# Voltmetro_3Digit_HADDAOUI.net
KiCad netlist of a schematic drawn in EAGLE
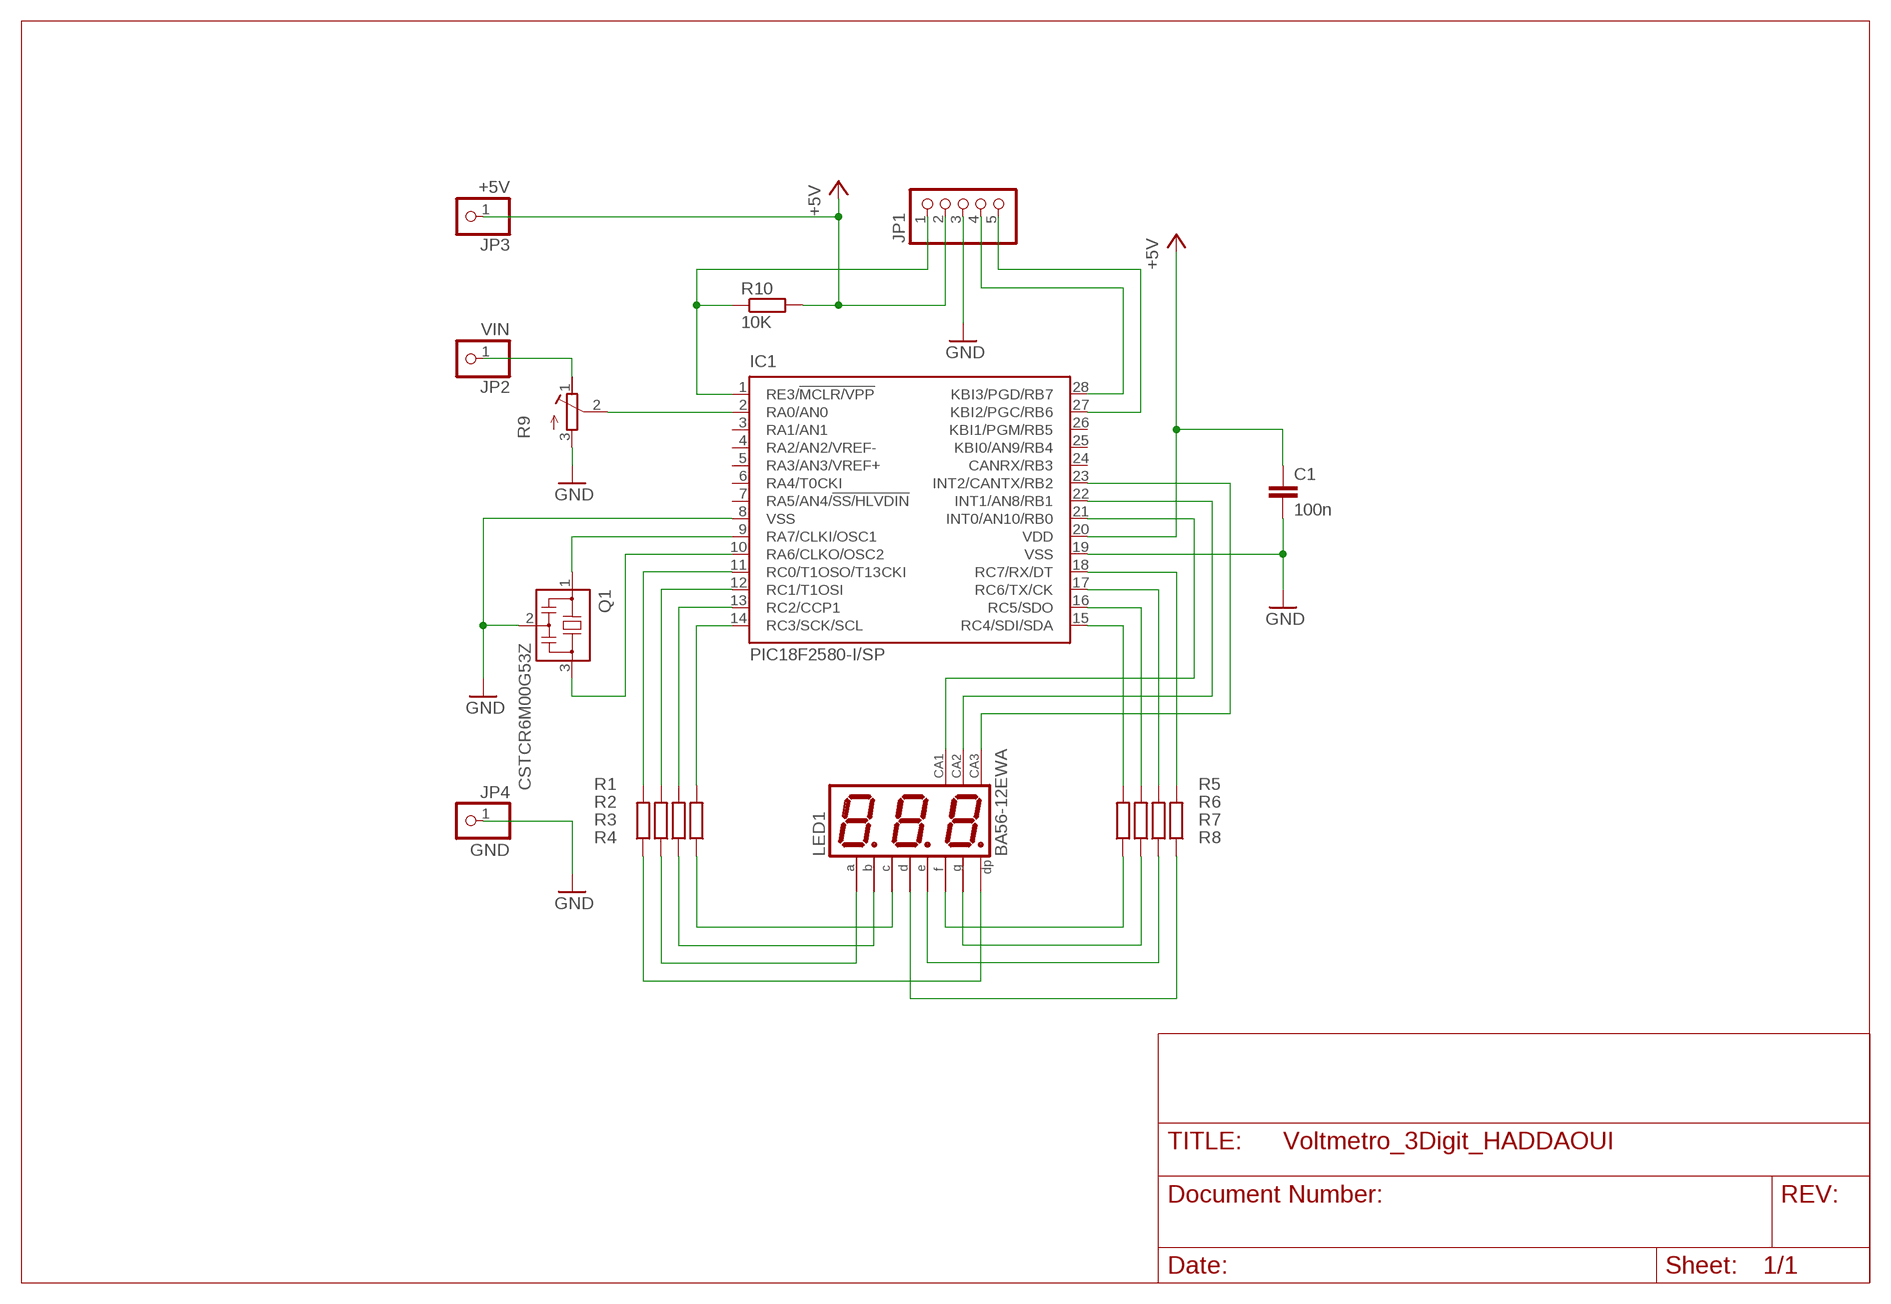
[diagram p0: schematic, sheet 1]

(export (version "E")
  (design (tool "Eeschema 10.0.6"))
  (components
    (comp (ref "C1")
      (value "100n")
      (footprint "eagle-import:C025-025X050")
      (libsource (lib "eagle-import") (part "C-EU025-025X050"))
    )
    (comp (ref "IC1")
      (value "PIC18F2580-I/SP")
      (footprint "eagle-import:DIL28-3")
      (fields (field (name "MF") "MICROCHIP"))
      (libsource (lib "eagle-import") (part "PIC18F280-I/SP5"))
    )
    (comp (ref "JP1")
      (value "PINHD-1X5")
      (footprint "eagle-import:1X05")
      (libsource (lib "eagle-import") (part "PINHD-1X5"))
    )
    (comp (ref "JP2")
      (value "VIN")
      (footprint "eagle-import:1X01")
      (libsource (lib "eagle-import") (part "PINHD-1X1"))
    )
    (comp (ref "JP3")
      (value "+5V")
      (footprint "eagle-import:1X01")
      (libsource (lib "eagle-import") (part "PINHD-1X1"))
    )
    (comp (ref "JP4")
      (value "GND")
      (footprint "eagle-import:1X01")
      (libsource (lib "eagle-import") (part "PINHD-1X1"))
    )
    (comp (ref "LED1")
      (value "BA56-12EWA")
      (footprint "eagle-import:BX56-12")
      (libsource (lib "eagle-import") (part "B?56-12WAAE"))
    )
    (comp (ref "Q1")
      (value "CSTCR6M00G53Z")
      (footprint "eagle-import:CSTCR6M")
      (fields (field (name "MPN") "CSTCR6M00G53-R0"))
      (libsource (lib "eagle-import") (part "CSTCR6M00G53Z"))
    )
    (comp (ref "R1")
      (value "R-EU_0204/7")
      (footprint "eagle-import:0204_7")
      (libsource (lib "eagle-import") (part "R-EU_0204/7"))
    )
    (comp (ref "R2")
      (value "R-EU_0204/7")
      (footprint "eagle-import:0204_7")
      (libsource (lib "eagle-import") (part "R-EU_0204/7"))
    )
    (comp (ref "R3")
      (value "R-EU_0204/7")
      (footprint "eagle-import:0204_7")
      (libsource (lib "eagle-import") (part "R-EU_0204/7"))
    )
    (comp (ref "R4")
      (value "R-EU_0204/7")
      (footprint "eagle-import:0204_7")
      (libsource (lib "eagle-import") (part "R-EU_0204/7"))
    )
    (comp (ref "R5")
      (value "R-EU_0204/7")
      (footprint "eagle-import:0204_7")
      (libsource (lib "eagle-import") (part "R-EU_0204/7"))
    )
    (comp (ref "R6")
      (value "R-EU_0204/7")
      (footprint "eagle-import:0204_7")
      (libsource (lib "eagle-import") (part "R-EU_0204/7"))
    )
    (comp (ref "R7")
      (value "R-EU_0204/7")
      (footprint "eagle-import:0204_7")
      (libsource (lib "eagle-import") (part "R-EU_0204/7"))
    )
    (comp (ref "R8")
      (value "R-EU_0204/7")
      (footprint "eagle-import:0204_7")
      (libsource (lib "eagle-import") (part "R-EU_0204/7"))
    )
    (comp (ref "R9")
      (value "R-TRIMM43P")
      (footprint "eagle-import:RTRIM43P")
      (libsource (lib "eagle-import") (part "R-TRIMM43P"))
    )
    (comp (ref "R10")
      (value "10K")
      (footprint "eagle-import:0204_7")
      (libsource (lib "eagle-import") (part "R-EU_0204/7"))
    )
  )
  (nets
    (net (code "1") (name "+5V") (class "Default")
      (node (ref "C1") (pin "1") (pinfunction "1_1") (pintype "passive"))
      (node (ref "IC1") (pin "20") (pinfunction "VDD_20") (pintype "power_in"))
      (node (ref "JP1") (pin "2") (pinfunction "2_2") (pintype "passive"))
      (node (ref "JP3") (pin "1") (pinfunction "1_1") (pintype "passive"))
      (node (ref "R10") (pin "2") (pinfunction "2_2") (pintype "passive"))
    )
    (net (code "2") (name "GND") (class "Default")
      (node (ref "C1") (pin "2") (pinfunction "2_2") (pintype "passive"))
      (node (ref "IC1") (pin "19") (pinfunction "VSS_19") (pintype "power_in"))
      (node (ref "IC1") (pin "8") (pinfunction "VSS_8") (pintype "power_in"))
      (node (ref "JP1") (pin "3") (pinfunction "3_3") (pintype "passive"))
      (node (ref "JP4") (pin "1") (pinfunction "1_1") (pintype "passive"))
      (node (ref "Q1") (pin "2") (pinfunction "2_2") (pintype "passive"))
      (node (ref "R9") (pin "3") (pinfunction "A_3") (pintype "passive"))
    )
    (net (code "3") (name "Net-(IC1-INT0{slash}AN10{slash}RB0)") (class "Default")
      (node (ref "IC1") (pin "21") (pinfunction "INT0/AN10/RB0_21") (pintype "bidirectional"))
      (node (ref "LED1") (pin "12") (pinfunction "CA_12") (pintype "passive"))
    )
    (net (code "4") (name "Net-(IC1-INT1{slash}AN8{slash}RB1)") (class "Default")
      (node (ref "IC1") (pin "22") (pinfunction "INT1/AN8/RB1_22") (pintype "bidirectional"))
      (node (ref "LED1") (pin "9") (pinfunction "CA_9") (pintype "passive"))
    )
    (net (code "5") (name "Net-(IC1-INT2{slash}CANTX{slash}RB2)") (class "Default")
      (node (ref "IC1") (pin "23") (pinfunction "INT2/CANTX/RB2_23") (pintype "bidirectional"))
      (node (ref "LED1") (pin "8") (pinfunction "CA_8") (pintype "passive"))
    )
    (net (code "6") (name "Net-(IC1-KBI2{slash}PGC{slash}RB6)") (class "Default")
      (node (ref "IC1") (pin "27") (pinfunction "KBI2/PGC/RB6_27") (pintype "bidirectional"))
      (node (ref "JP1") (pin "5") (pinfunction "5_5") (pintype "passive"))
    )
    (net (code "7") (name "Net-(IC1-KBI3{slash}PGD{slash}RB7)") (class "Default")
      (node (ref "IC1") (pin "28") (pinfunction "KBI3/PGD/RB7_28") (pintype "bidirectional"))
      (node (ref "JP1") (pin "4") (pinfunction "4_4") (pintype "passive"))
    )
    (net (code "8") (name "Net-(IC1-RA0{slash}AN0)") (class "Default")
      (node (ref "IC1") (pin "2") (pinfunction "RA0/AN0_2") (pintype "bidirectional"))
      (node (ref "R9") (pin "2") (pinfunction "S_2") (pintype "passive"))
    )
    (net (code "9") (name "Net-(IC1-RA6{slash}CLKO{slash}OSC2)") (class "Default")
      (node (ref "IC1") (pin "10") (pinfunction "RA6/CLKO/OSC2_10") (pintype "output"))
      (node (ref "Q1") (pin "3") (pinfunction "3_3") (pintype "passive"))
    )
    (net (code "10") (name "Net-(IC1-RA7{slash}CLKI{slash}OSC1)") (class "Default")
      (node (ref "IC1") (pin "9") (pinfunction "RA7/CLKI/OSC1_9") (pintype "input"))
      (node (ref "Q1") (pin "1") (pinfunction "1_1") (pintype "passive"))
    )
    (net (code "11") (name "Net-(IC1-RC0{slash}T1OSO{slash}T13CKI)") (class "Default")
      (node (ref "IC1") (pin "11") (pinfunction "RC0/T1OSO/T13CKI_11") (pintype "bidirectional"))
      (node (ref "R1") (pin "2") (pinfunction "2_2") (pintype "passive"))
    )
    (net (code "12") (name "Net-(IC1-RC1{slash}T1OSI)") (class "Default")
      (node (ref "IC1") (pin "12") (pinfunction "RC1/T1OSI_12") (pintype "bidirectional"))
      (node (ref "R2") (pin "2") (pinfunction "2_2") (pintype "passive"))
    )
    (net (code "13") (name "Net-(IC1-RC2{slash}CCP1)") (class "Default")
      (node (ref "IC1") (pin "13") (pinfunction "RC2/CCP1_13") (pintype "bidirectional"))
      (node (ref "R3") (pin "2") (pinfunction "2_2") (pintype "passive"))
    )
    (net (code "14") (name "Net-(IC1-RC3{slash}SCK{slash}SCL)") (class "Default")
      (node (ref "IC1") (pin "14") (pinfunction "RC3/SCK/SCL_14") (pintype "bidirectional"))
      (node (ref "R4") (pin "2") (pinfunction "2_2") (pintype "passive"))
    )
    (net (code "15") (name "Net-(IC1-RC4{slash}SDI{slash}SDA)") (class "Default")
      (node (ref "IC1") (pin "15") (pinfunction "RC4/SDI/SDA_15") (pintype "bidirectional"))
      (node (ref "R5") (pin "2") (pinfunction "2_2") (pintype "passive"))
    )
    (net (code "16") (name "Net-(IC1-RC5{slash}SDO)") (class "Default")
      (node (ref "IC1") (pin "16") (pinfunction "RC5/SDO_16") (pintype "bidirectional"))
      (node (ref "R6") (pin "2") (pinfunction "2_2") (pintype "passive"))
    )
    (net (code "17") (name "Net-(IC1-RC6{slash}TX{slash}CK)") (class "Default")
      (node (ref "IC1") (pin "17") (pinfunction "RC6/TX/CK_17") (pintype "bidirectional"))
      (node (ref "R7") (pin "2") (pinfunction "2_2") (pintype "passive"))
    )
    (net (code "18") (name "Net-(IC1-RC7{slash}RX{slash}DT)") (class "Default")
      (node (ref "IC1") (pin "18") (pinfunction "RC7/RX/DT_18") (pintype "bidirectional"))
      (node (ref "R8") (pin "2") (pinfunction "2_2") (pintype "passive"))
    )
    (net (code "19") (name "Net-(IC1-RE3{slash}~{MCLR{slash}VPP})") (class "Default")
      (node (ref "IC1") (pin "1") (pinfunction "RE3/~{MCLR/VPP}_1") (pintype "input"))
      (node (ref "JP1") (pin "1") (pinfunction "1_1") (pintype "passive"))
      (node (ref "R10") (pin "1") (pinfunction "1_1") (pintype "passive"))
    )
    (net (code "20") (name "Net-(LED1-A)") (class "Default")
      (node (ref "LED1") (pin "11") (pinfunction "A_11") (pintype "passive"))
      (node (ref "R2") (pin "1") (pinfunction "1_1") (pintype "passive"))
    )
    (net (code "21") (name "Net-(LED1-B)") (class "Default")
      (node (ref "LED1") (pin "7") (pinfunction "B_7") (pintype "passive"))
      (node (ref "R3") (pin "1") (pinfunction "1_1") (pintype "passive"))
    )
    (net (code "22") (name "Net-(LED1-C)") (class "Default")
      (node (ref "LED1") (pin "4") (pinfunction "C_4") (pintype "passive"))
      (node (ref "R4") (pin "1") (pinfunction "1_1") (pintype "passive"))
    )
    (net (code "23") (name "Net-(LED1-D)") (class "Default")
      (node (ref "LED1") (pin "2") (pinfunction "D_2") (pintype "passive"))
      (node (ref "R8") (pin "1") (pinfunction "1_1") (pintype "passive"))
    )
    (net (code "24") (name "Net-(LED1-DP)") (class "Default")
      (node (ref "LED1") (pin "3") (pinfunction "DP_3") (pintype "passive"))
      (node (ref "R1") (pin "1") (pinfunction "1_1") (pintype "passive"))
    )
    (net (code "25") (name "Net-(LED1-E)") (class "Default")
      (node (ref "LED1") (pin "1") (pinfunction "E_1") (pintype "passive"))
      (node (ref "R7") (pin "1") (pinfunction "1_1") (pintype "passive"))
    )
    (net (code "26") (name "Net-(LED1-F)") (class "Default")
      (node (ref "LED1") (pin "10") (pinfunction "F_10") (pintype "passive"))
      (node (ref "R5") (pin "1") (pinfunction "1_1") (pintype "passive"))
    )
    (net (code "27") (name "Net-(LED1-G)") (class "Default")
      (node (ref "LED1") (pin "5") (pinfunction "G_5") (pintype "passive"))
      (node (ref "R6") (pin "1") (pinfunction "1_1") (pintype "passive"))
    )
    (net (code "28") (name "Net-(R9-E)") (class "Default")
      (node (ref "JP2") (pin "1") (pinfunction "1_1") (pintype "passive"))
      (node (ref "R9") (pin "1") (pinfunction "E_1") (pintype "passive"))
    )
    (net (code "29") (name "unconnected-(IC1-CANRX{slash}RB3-Pad24)") (class "Default")
      (node (ref "IC1") (pin "24") (pinfunction "CANRX/RB3_24") (pintype "bidirectional"))
    )
    (net (code "30") (name "unconnected-(IC1-KBI0{slash}AN9{slash}RB4-Pad25)") (class "Default")
      (node (ref "IC1") (pin "25") (pinfunction "KBI0/AN9/RB4_25") (pintype "bidirectional"))
    )
    (net (code "31") (name "unconnected-(IC1-KBI1{slash}PGM{slash}RB5-Pad26)") (class "Default")
      (node (ref "IC1") (pin "26") (pinfunction "KBI1/PGM/RB5_26") (pintype "bidirectional"))
    )
    (net (code "32") (name "unconnected-(IC1-RA1{slash}AN1-Pad3)") (class "Default")
      (node (ref "IC1") (pin "3") (pinfunction "RA1/AN1_3") (pintype "bidirectional"))
    )
    (net (code "33") (name "unconnected-(IC1-RA2{slash}AN2{slash}VREF--Pad4)") (class "Default")
      (node (ref "IC1") (pin "4") (pinfunction "RA2/AN2/VREF-_4") (pintype "bidirectional"))
    )
    (net (code "34") (name "unconnected-(IC1-RA3{slash}AN3{slash}VREF+-Pad5)") (class "Default")
      (node (ref "IC1") (pin "5") (pinfunction "RA3/AN3/VREF+_5") (pintype "bidirectional"))
    )
    (net (code "35") (name "unconnected-(IC1-RA4{slash}T0CKI-Pad6)") (class "Default")
      (node (ref "IC1") (pin "6") (pinfunction "RA4/T0CKI_6") (pintype "bidirectional"))
    )
    (net (code "36") (name "unconnected-(IC1-RA5{slash}AN4{slash}~{SS{slash}HLVDIN}-Pad7)") (class "Default")
      (node (ref "IC1") (pin "7") (pinfunction "RA5/AN4/~{SS/HLVDIN}_7") (pintype "bidirectional"))
    )
  )
)
